# Sheet2.net
KiCad netlist of a schematic drawn in Altium Designer
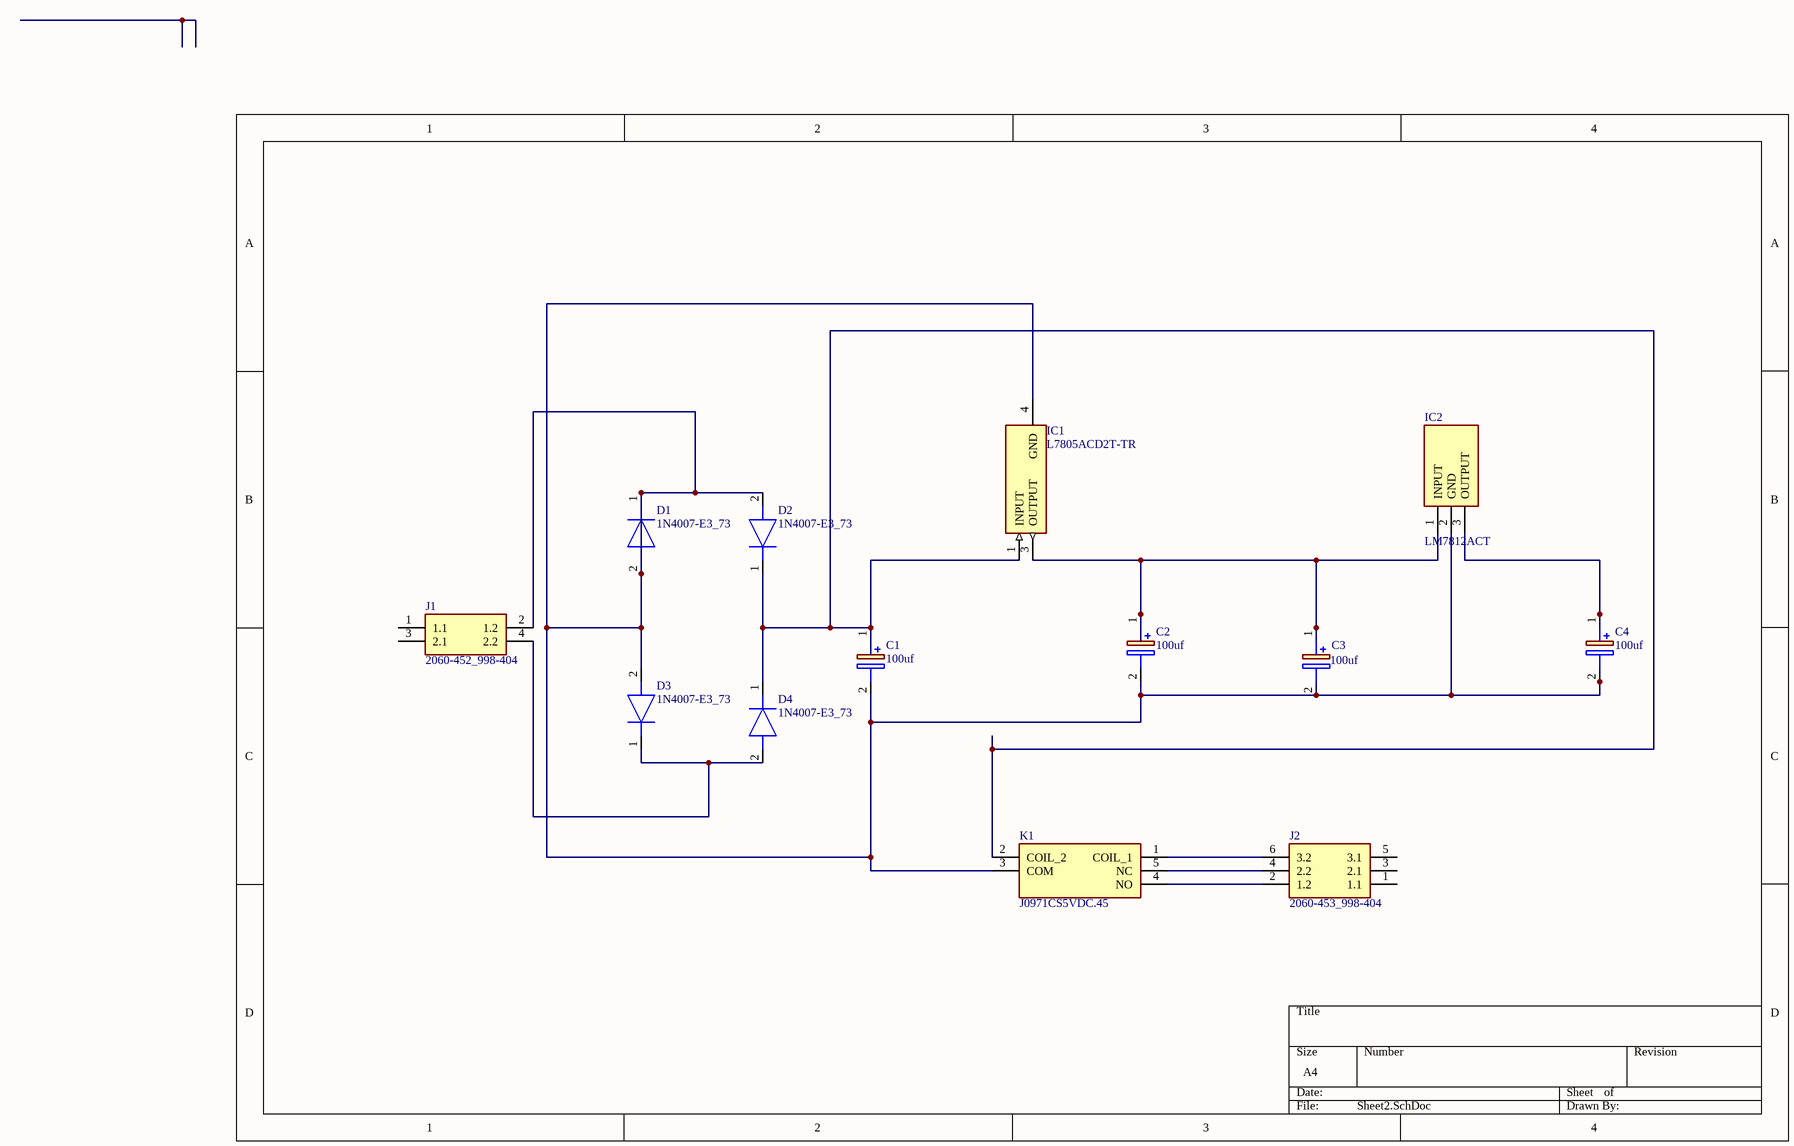
[diagram p0: Sheet2.SchDoc]

(export (version "E")
  (design (tool "Eeschema 10.0.6"))
  (components
    (comp (ref "C1")
      (value "100uf")
      (footprint "SamacSys:CAPPRD500W65D1250H2700")
      (description "Capacitor Polarised")
      (fields (field (name "MANUFACTURER_PART_NUMBER") "EEUTA1E102LB"))
      (libsource (lib "*") (part "EEUTA1E102LB"))
    )
    (comp (ref "C2")
      (value "100uf")
      (footprint "SamacSys:CAPPRD500W65D1250H2700")
      (description "Capacitor Polarised")
      (fields (field (name "MANUFACTURER_PART_NUMBER") "EEUTA1E102LB"))
      (libsource (lib "*") (part "EEUTA1E102LB"))
    )
    (comp (ref "C3")
      (value "100uf")
      (footprint "SamacSys:CAPPRD500W65D1250H2700")
      (description "Capacitor Polarised")
      (fields (field (name "MANUFACTURER_PART_NUMBER") "EEUTA1E102LB"))
      (libsource (lib "*") (part "EEUTA1E102LB"))
    )
    (comp (ref "C4")
      (value "100uf")
      (footprint "SamacSys:CAPPRD500W65D1250H2700")
      (description "Capacitor Polarised")
      (fields (field (name "MANUFACTURER_PART_NUMBER") "EEUTA1E102LB"))
      (libsource (lib "*") (part "EEUTA1E102LB"))
    )
    (comp (ref "D1")
      (value "1N4007-E3_73")
      (footprint "SamacSys:DIOAD1405W86L465D235")
      (description "Diode")
      (fields
        (field (name "MANUFACTURER_PART_NUMBER") "1N4007-E3/73")
        (field (name "MOUSER PART NUMBER") "625-1N4007-E3/73")
      )
      (libsource (lib "SamacSys") (part "1N4007-E3_73"))
    )
    (comp (ref "D2")
      (value "1N4007-E3_73")
      (footprint "SamacSys:DIOAD1405W86L465D235")
      (description "Diode")
      (fields
        (field (name "MANUFACTURER_PART_NUMBER") "1N4007-E3/73")
        (field (name "MOUSER PART NUMBER") "625-1N4007-E3/73")
      )
      (libsource (lib "SamacSys") (part "1N4007-E3_73"))
    )
    (comp (ref "D3")
      (value "1N4007-E3_73")
      (footprint "SamacSys:DIOAD1405W86L465D235")
      (description "Diode")
      (fields
        (field (name "MANUFACTURER_PART_NUMBER") "1N4007-E3/73")
        (field (name "MOUSER PART NUMBER") "625-1N4007-E3/73")
      )
      (libsource (lib "SamacSys") (part "1N4007-E3_73"))
    )
    (comp (ref "D4")
      (value "1N4007-E3_73")
      (footprint "SamacSys:DIOAD1405W86L465D235")
      (description "Diode")
      (fields
        (field (name "MANUFACTURER_PART_NUMBER") "1N4007-E3/73")
        (field (name "MOUSER PART NUMBER") "625-1N4007-E3/73")
      )
      (libsource (lib "SamacSys") (part "1N4007-E3_73"))
    )
    (comp (ref "IC1")
      (value "L7805ACD2T-TR")
      (footprint "SamacSys:D2PAK-STB35NF10T4")
      (description "Integrated Circuit")
      (fields (field (name "MOUSER PART NUMBER") "511-L7805ACD2T-TR"))
      (libsource (lib "*") (part "L7805ACD2T-TR"))
    )
    (comp (ref "IC2")
      (value "LM7812ACT")
      (footprint "SamacSys:TO254P470X1016X2019-3P")
      (description "Integrated Circuit")
      (fields (field (name "MOUSER PART NUMBER") "512-LM7812ACT"))
      (libsource (lib "SamacSys") (part "LM7812ACT"))
    )
    (comp (ref "J1")
      (value "2060-452_998-404")
      (footprint "SamacSys:2060452998404")
      (description "Connector")
      (fields (field (name "MANUFACTURER_PART_NUMBER") "2060-452/998-404"))
      (libsource (lib "*") (part "2060-452_998-404"))
    )
    (comp (ref "J2")
      (value "2060-453_998-404")
      (footprint "SamacSys:2060453998404")
      (description "Connector")
      (fields (field (name "MANUFACTURER_PART_NUMBER") "2060-453/998-404"))
      (libsource (lib "*") (part "2060-453_998-404"))
    )
    (comp (ref "K1")
      (value "J0971CS5VDC.45")
      (footprint "SamacSys:J0971CS5VDC45")
      (description "Relay or Contactor")
      (libsource (lib "*") (part "J0971CS5VDC.45"))
    )
  )
  (nets
    (net (code "1") (name "Net-(C1-+)") (class "Default")
      (node (ref "C1") (pin "1") (pinfunction "+_1") (pintype "passive"))
      (node (ref "D2") (pin "1") (pinfunction "K_1") (pintype "passive"))
      (node (ref "D4") (pin "1") (pinfunction "K_1") (pintype "passive"))
      (node (ref "IC1") (pin "1") (pinfunction "INPUT_1") (pintype "input"))
      (node (ref "K1") (pin "2") (pinfunction "COIL_2_2") (pintype "passive"))
    )
    (net (code "2") (name "Net-(C1--)") (class "Default")
      (node (ref "C1") (pin "2") (pinfunction "-_2") (pintype "passive"))
      (node (ref "C2") (pin "2") (pinfunction "-_2") (pintype "passive"))
      (node (ref "C3") (pin "2") (pinfunction "-_2") (pintype "passive"))
      (node (ref "C4") (pin "2") (pinfunction "-_2") (pintype "passive"))
      (node (ref "D1") (pin "1") (pinfunction "K_1") (pintype "passive"))
      (node (ref "D1") (pin "2") (pinfunction "A_2") (pintype "passive"))
      (node (ref "D2") (pin "2") (pinfunction "A_2") (pintype "passive"))
      (node (ref "D3") (pin "2") (pinfunction "A_2") (pintype "passive"))
      (node (ref "IC1") (pin "4") (pinfunction "GND_4") (pintype "power_in"))
      (node (ref "IC2") (pin "2") (pinfunction "GND_2") (pintype "passive"))
      (node (ref "J1") (pin "2") (pinfunction "1.2_2") (pintype "passive"))
      (node (ref "K1") (pin "3") (pinfunction "COM_3") (pintype "passive"))
    )
    (net (code "3") (name "Net-(C2-+)") (class "Default")
      (node (ref "C2") (pin "1") (pinfunction "+_1") (pintype "passive"))
      (node (ref "C3") (pin "1") (pinfunction "+_1") (pintype "passive"))
      (node (ref "IC1") (pin "3") (pinfunction "OUTPUT_3") (pintype "output"))
      (node (ref "IC2") (pin "1") (pinfunction "INPUT_1") (pintype "passive"))
    )
    (net (code "4") (name "Net-(C4-+)") (class "Default")
      (node (ref "C4") (pin "1") (pinfunction "+_1") (pintype "passive"))
      (node (ref "IC2") (pin "3") (pinfunction "OUTPUT_3") (pintype "passive"))
    )
    (net (code "5") (name "Net-(D3-K)") (class "Default")
      (node (ref "D3") (pin "1") (pinfunction "K_1") (pintype "passive"))
      (node (ref "D4") (pin "2") (pinfunction "A_2") (pintype "passive"))
      (node (ref "J1") (pin "4") (pinfunction "2.2_4") (pintype "passive"))
    )
    (net (code "6") (name "Net-(J2-1.2)") (class "Default")
      (node (ref "J2") (pin "2") (pinfunction "1.2_2") (pintype "passive"))
      (node (ref "K1") (pin "4") (pinfunction "NO_4") (pintype "passive"))
    )
    (net (code "7") (name "Net-(J2-2.2)") (class "Default")
      (node (ref "J2") (pin "4") (pinfunction "2.2_4") (pintype "passive"))
      (node (ref "K1") (pin "5") (pinfunction "NC_5") (pintype "passive"))
    )
    (net (code "8") (name "Net-(J2-3.2)") (class "Default")
      (node (ref "J2") (pin "6") (pinfunction "3.2_6") (pintype "passive"))
      (node (ref "K1") (pin "1") (pinfunction "COIL_1_1") (pintype "passive"))
    )
    (net (code "9") (name "unconnected-(J1-1.1-Pad1)") (class "Default")
      (node (ref "J1") (pin "1") (pinfunction "1.1_1") (pintype "passive"))
    )
    (net (code "10") (name "unconnected-(J1-2.1-Pad3)") (class "Default")
      (node (ref "J1") (pin "3") (pinfunction "2.1_3") (pintype "passive"))
    )
    (net (code "11") (name "unconnected-(J2-1.1-Pad1)") (class "Default")
      (node (ref "J2") (pin "1") (pinfunction "1.1_1") (pintype "passive"))
    )
    (net (code "12") (name "unconnected-(J2-2.1-Pad3)") (class "Default")
      (node (ref "J2") (pin "3") (pinfunction "2.1_3") (pintype "passive"))
    )
    (net (code "13") (name "unconnected-(J2-3.1-Pad5)") (class "Default")
      (node (ref "J2") (pin "5") (pinfunction "3.1_5") (pintype "passive"))
    )
  )
)
